# DM1098EMB_TopLevel.net
KiCad netlist of a schematic drawn in Altium Designer
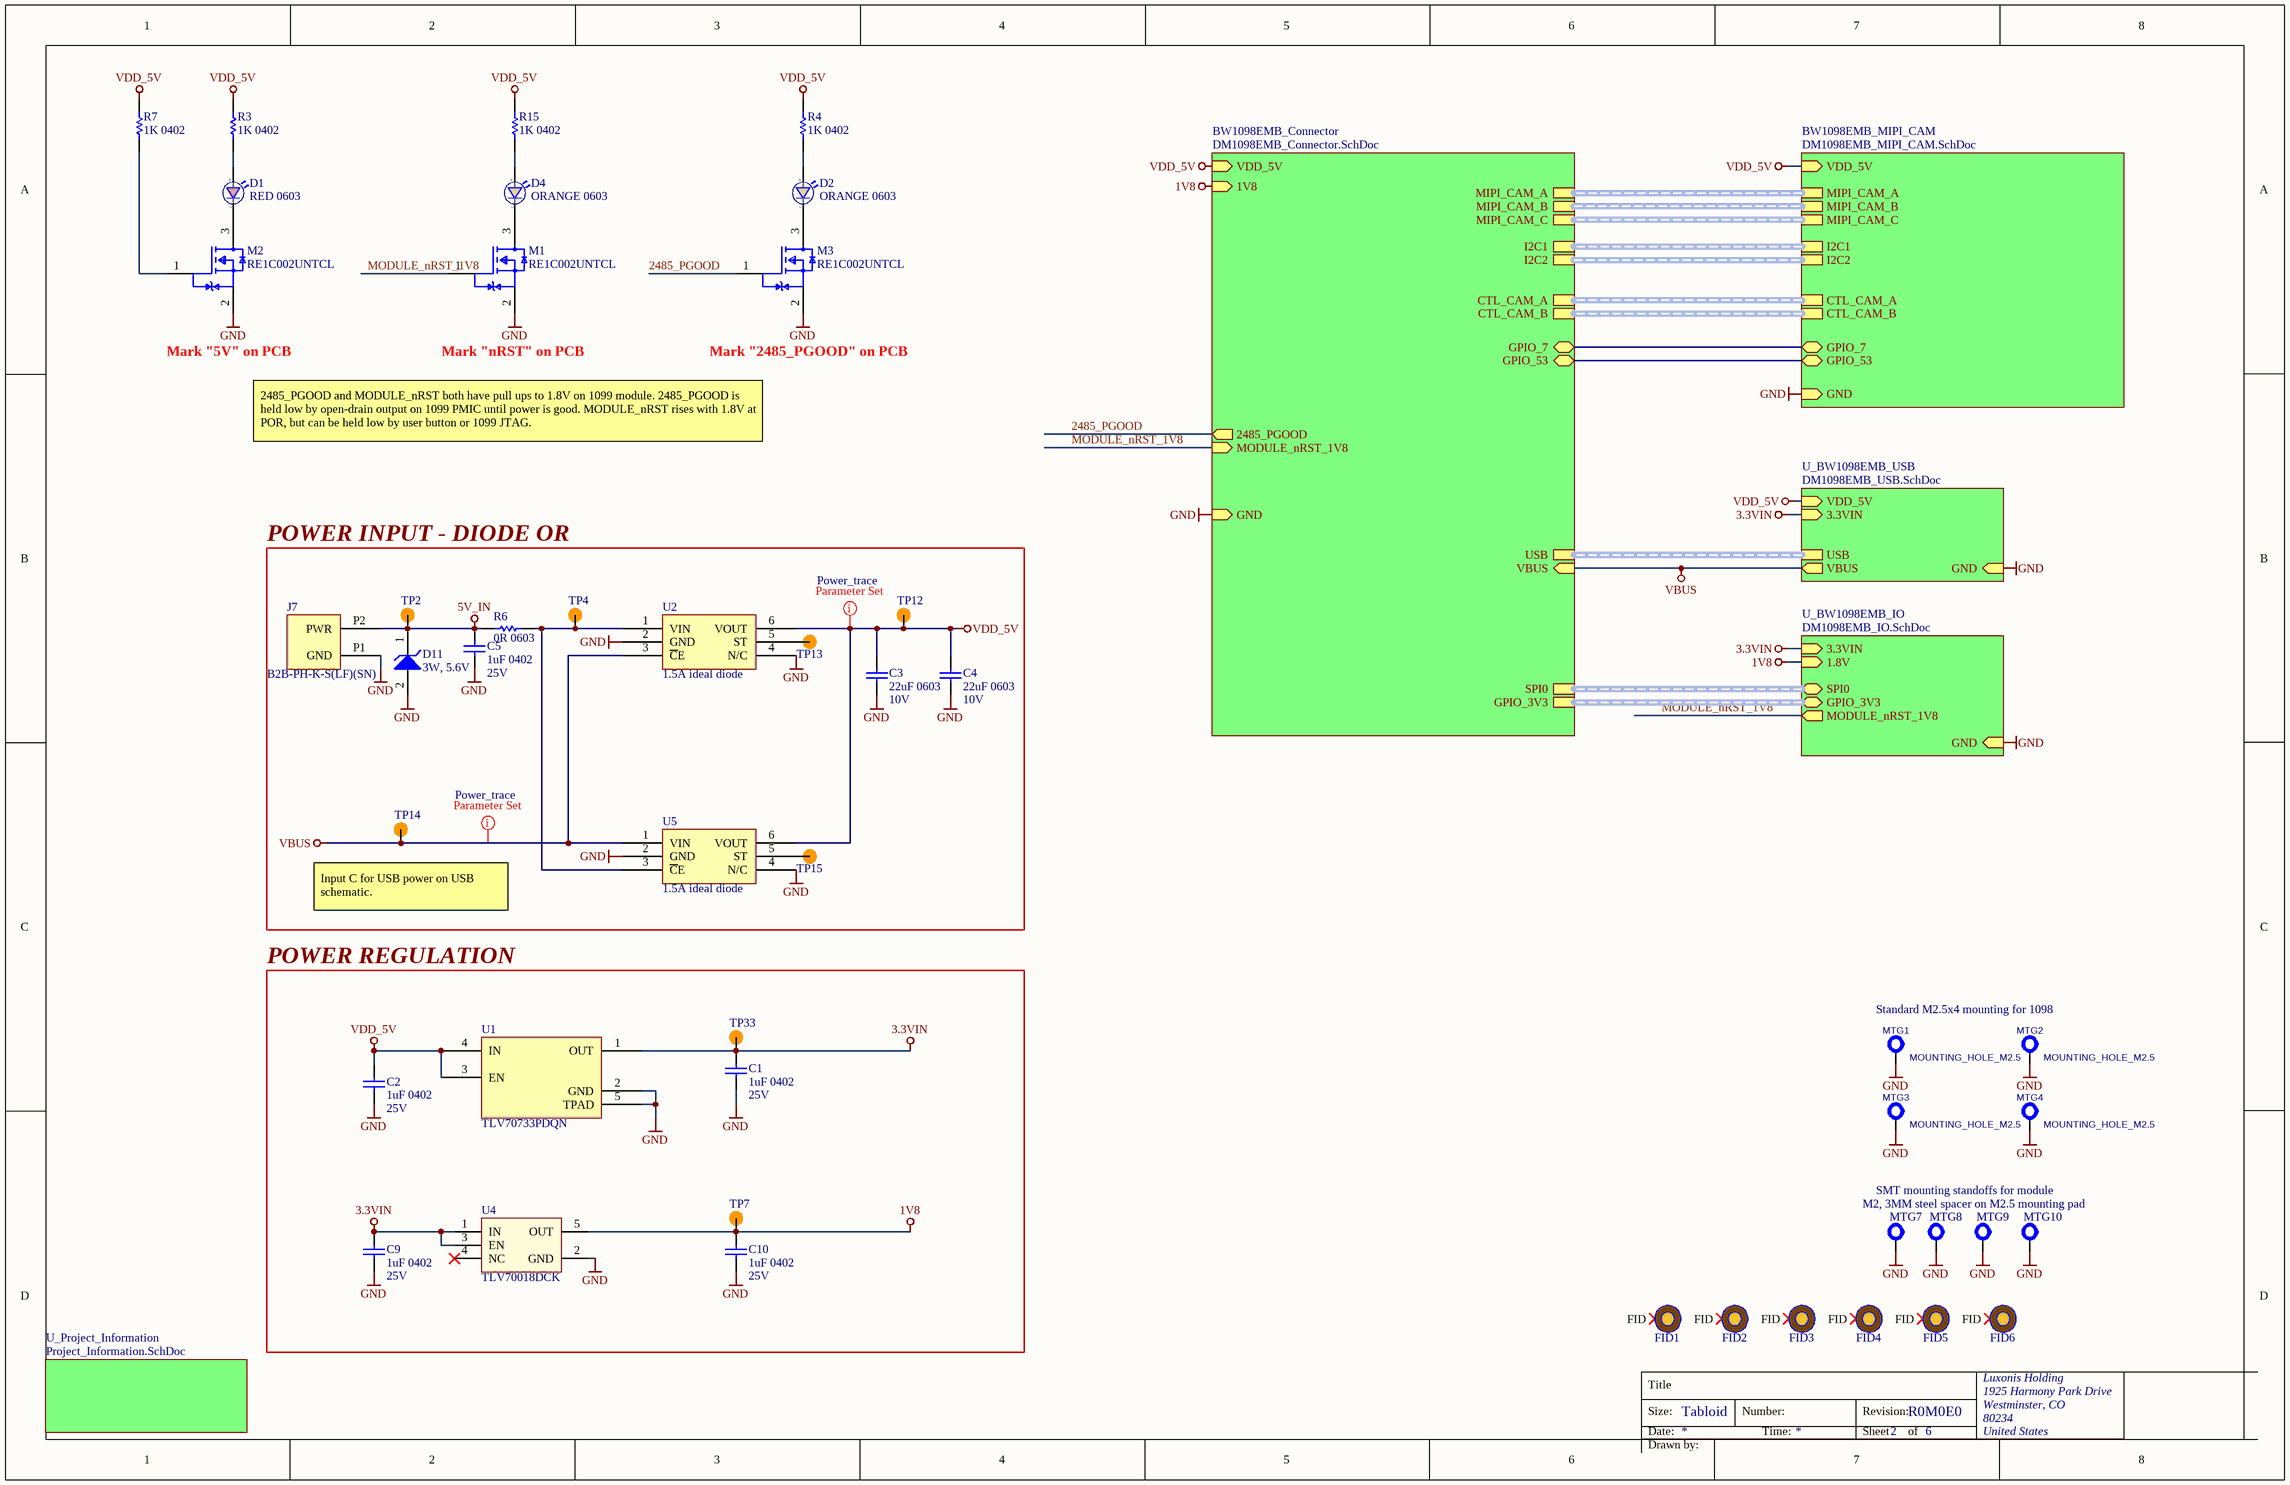
[diagram p0: DM1098EMB_TopLevel.SchDoc]

(export (version "E")
  (design (tool "Eeschema 10.0.6"))
  (components
    (comp (ref "C1")
      (value "1uF 0402")
      (footprint "CAP_Altium_Vault_Generic:CAPC0402(1005)70_N")
      (description "CAP CER 1UF 25V X5R 0402 10%")
      (fields
        (field (name "TOLERANCE") "10%")
        (field (name "VOLTAGE") "25V")
        (field (name "VOLTAGE RATING") "25V")
      )
      (libsource (lib "LuxonisMaster") (part "GRM155R61E105KA12D"))
    )
    (comp (ref "C2")
      (value "1uF 0402")
      (footprint "CAP_Altium_Vault_Generic:CAPC0402(1005)70_N")
      (description "CAP CER 1UF 25V X5R 0402 10%")
      (fields
        (field (name "TOLERANCE") "10%")
        (field (name "VOLTAGE") "25V")
        (field (name "VOLTAGE RATING") "25V")
      )
      (libsource (lib "LuxonisMaster") (part "GRM155R61E105KA12D"))
    )
    (comp (ref "C3")
      (value "22uF 0603")
      (footprint "CAP_Altium_Vault_Generic:CAPC0603(1608)100_N")
      (description "CAP CER 22UF 10V X5R 0603 20%")
      (fields (field (name "TOLERANCE") "20%") (field (name "VOLTAGE RATING") "10V"))
      (libsource (lib "LuxonisMaster") (part "GRM188R61A226ME15D"))
    )
    (comp (ref "C4")
      (value "22uF 0603")
      (footprint "CAP_Altium_Vault_Generic:CAPC0603(1608)100_N")
      (description "CAP CER 22UF 10V X5R 0603 20%")
      (fields (field (name "TOLERANCE") "20%") (field (name "VOLTAGE RATING") "10V"))
      (libsource (lib "LuxonisMaster") (part "GRM188R61A226ME15D"))
    )
    (comp (ref "C5")
      (value "1uF 0402")
      (footprint "CAP_Altium_Vault_Generic:CAPC0402(1005)70_N")
      (description "CAP CER 1UF 25V X5R 0402 10%")
      (fields
        (field (name "TOLERANCE") "10%")
        (field (name "VOLTAGE") "25V")
        (field (name "VOLTAGE RATING") "25V")
      )
      (libsource (lib "LuxonisMaster") (part "GRM155R61E105KA12D"))
    )
    (comp (ref "C9")
      (value "1uF 0402")
      (footprint "CAP_Altium_Vault_Generic:CAPC0402(1005)70_N")
      (description "CAP CER 1UF 25V X5R 0402 10%")
      (fields
        (field (name "TOLERANCE") "10%")
        (field (name "VOLTAGE") "25V")
        (field (name "VOLTAGE RATING") "25V")
      )
      (libsource (lib "LuxonisMaster") (part "GRM155R61E105KA12D"))
    )
    (comp (ref "C10")
      (value "1uF 0402")
      (footprint "CAP_Altium_Vault_Generic:CAPC0402(1005)70_N")
      (description "CAP CER 1UF 25V X5R 0402 10%")
      (fields
        (field (name "TOLERANCE") "10%")
        (field (name "VOLTAGE") "25V")
        (field (name "VOLTAGE RATING") "25V")
      )
      (libsource (lib "LuxonisMaster") (part "GRM155R61E105KA12D"))
    )
    (comp (ref "D1")
      (value "RED 0603")
      (footprint "LuxonisMaster:SML_D1xx8W")
      (description "LED RED DIFFUSED 0603 SMD Red 620nm LED Indication - Discrete 2.2V 0603 (1608 Metric)")
      (libsource (lib "LuxonisMaster") (part "SML-D12U8WT86"))
    )
    (comp (ref "D2")
      (value "ORANGE 0603")
      (footprint "LuxonisMaster:SML_D1xx8W")
      (description "LED ORANGE DIFFUSED 0603 SMD Orange 605nm LED Indication - Discrete 2.2V 0603 (1608 Metric)")
      (libsource (lib "LuxonisMaster") (part "SML-D12D8WT86"))
    )
    (comp (ref "D4")
      (value "ORANGE 0603")
      (footprint "LuxonisMaster:SML_D1xx8W")
      (description "LED ORANGE DIFFUSED 0603 SMD Orange 605nm LED Indication - Discrete 2.2V 0603 (1608 Metric)")
      (libsource (lib "LuxonisMaster") (part "SML-D12D8WT86"))
    )
    (comp (ref "D11")
      (value "3W, 5.6V")
      (footprint "DM1092_R0M0E0:1SMB5919BT3G")
      (description "DIODE ZENER 5.6V 3W SMB")
      (fields (field (name "TOLERANCE") "5%"))
      (libsource (lib "DM1092_R0M0E0") (part "1SMB5919BT3G"))
    )
    (comp (ref "FID1")
      (value "FIDUCIAL_ROUND_1MM")
      (footprint "LuxonisMaster:FIDUCIAL_ROUND_1MM")
      (description "Fiducial with various available footprints")
      (libsource (lib "LuxonisMaster") (part "FIDUCIAL"))
    )
    (comp (ref "FID2")
      (value "FIDUCIAL_ROUND_1MM")
      (footprint "LuxonisMaster:FIDUCIAL_ROUND_1MM")
      (description "Fiducial with various available footprints")
      (libsource (lib "LuxonisMaster") (part "FIDUCIAL"))
    )
    (comp (ref "FID3")
      (value "FIDUCIAL_ROUND_1MM")
      (footprint "LuxonisMaster:FIDUCIAL_ROUND_1MM")
      (description "Fiducial with various available footprints")
      (libsource (lib "LuxonisMaster") (part "FIDUCIAL"))
    )
    (comp (ref "FID4")
      (value "FIDUCIAL_ROUND_1MM")
      (footprint "LuxonisMaster:FIDUCIAL_ROUND_1MM")
      (description "Fiducial with various available footprints")
      (libsource (lib "LuxonisMaster") (part "FIDUCIAL"))
    )
    (comp (ref "FID5")
      (value "FIDUCIAL_ROUND_1MM")
      (footprint "LuxonisMaster:FIDUCIAL_ROUND_1MM")
      (description "Fiducial with various available footprints")
      (libsource (lib "LuxonisMaster") (part "FIDUCIAL"))
    )
    (comp (ref "FID6")
      (value "FIDUCIAL_ROUND_1MM")
      (footprint "LuxonisMaster:FIDUCIAL_ROUND_1MM")
      (description "Fiducial with various available footprints")
      (libsource (lib "LuxonisMaster") (part "FIDUCIAL"))
    )
    (comp (ref "J7")
      (value "B2B-PH-K-S(LF)(SN)")
      (footprint "LuxonisMaster:B2B-PH-K-S(LF)(SN)")
      (description "CONN HEADER VERT 2POS 2MM")
      (libsource (lib "LuxonisMaster") (part "B2B-PH-K-S(LF)(SN)"))
    )
    (comp (ref "M1")
      (value "RE1C002UNTCL")
      (footprint "LuxonisMaster:RE1C002UNTCL")
      (description "MOSFET N-CH 20V 0.2A EMT3")
      (libsource (lib "LuxonisMaster") (part "RE1C002UNTCL"))
    )
    (comp (ref "M2")
      (value "RE1C002UNTCL")
      (footprint "LuxonisMaster:RE1C002UNTCL")
      (description "MOSFET N-CH 20V 0.2A EMT3")
      (libsource (lib "LuxonisMaster") (part "RE1C002UNTCL"))
    )
    (comp (ref "M3")
      (value "RE1C002UNTCL")
      (footprint "LuxonisMaster:RE1C002UNTCL")
      (description "MOSFET N-CH 20V 0.2A EMT3")
      (libsource (lib "LuxonisMaster") (part "RE1C002UNTCL"))
    )
    (comp (ref "MTG1")
      (value "MOUNTING_HOLE_M2.5")
      (footprint "LuxonisMaster:MOUNTING_HOLE_M2.5")
      (description "=CurrentFootprint")
      (libsource (lib "LuxonisMaster") (part "MP_Mounting-Holes"))
    )
    (comp (ref "MTG2")
      (value "MOUNTING_HOLE_M2.5")
      (footprint "LuxonisMaster:MOUNTING_HOLE_M2.5")
      (description "=CurrentFootprint")
      (libsource (lib "LuxonisMaster") (part "MP_Mounting-Holes"))
    )
    (comp (ref "MTG3")
      (value "MOUNTING_HOLE_M2.5")
      (footprint "LuxonisMaster:MOUNTING_HOLE_M2.5")
      (description "=CurrentFootprint")
      (libsource (lib "LuxonisMaster") (part "MP_Mounting-Holes"))
    )
    (comp (ref "MTG4")
      (value "MOUNTING_HOLE_M2.5")
      (footprint "LuxonisMaster:MOUNTING_HOLE_M2.5")
      (description "=CurrentFootprint")
      (libsource (lib "LuxonisMaster") (part "MP_Mounting-Holes"))
    )
    (comp (ref "MTG7")
      (value "M2, 3MM steel spacer on M2.5 mounting pad")
      (footprint "LuxonisMaster:9774030243R")
      (description "MP ROUND STANDOFF M2X0.4 STEEL 3MM")
      (libsource (lib "LuxonisMaster") (part "9774030243R"))
    )
    (comp (ref "MTG8")
      (value "M2, 3MM steel spacer on M2.5 mounting pad")
      (footprint "LuxonisMaster:9774030243R")
      (description "MP ROUND STANDOFF M2X0.4 STEEL 3MM")
      (libsource (lib "LuxonisMaster") (part "9774030243R"))
    )
    (comp (ref "MTG9")
      (value "M2, 3MM steel spacer on M2.5 mounting pad")
      (footprint "LuxonisMaster:9774030243R")
      (description "MP ROUND STANDOFF M2X0.4 STEEL 3MM")
      (libsource (lib "LuxonisMaster") (part "9774030243R"))
    )
    (comp (ref "MTG10")
      (value "M2, 3MM steel spacer on M2.5 mounting pad")
      (footprint "LuxonisMaster:9774030243R")
      (description "MP ROUND STANDOFF M2X0.4 STEEL 3MM")
      (libsource (lib "LuxonisMaster") (part "9774030243R"))
    )
    (comp (ref "R3")
      (value "1K 0402")
      (footprint "RES_Altium_Vault_Generic:RESC0402(1005)_N")
      (fields (field (name "TOLERANCE") "1%"))
      (libsource (lib "LuxonisMaster") (part "RC0402FR-071KL"))
    )
    (comp (ref "R4")
      (value "1K 0402")
      (footprint "RES_Altium_Vault_Generic:RESC0402(1005)_N")
      (fields (field (name "TOLERANCE") "1%"))
      (libsource (lib "LuxonisMaster") (part "RC0402FR-071KL"))
    )
    (comp (ref "R6")
      (value "0R 0603")
      (footprint "RES_Altium_Vault_Generic:RESC0603(1608)_N")
      (fields (field (name "TOLERANCE") "5%"))
      (libsource (lib "LuxonisMaster") (part "CRCW06030000Z0EA"))
    )
    (comp (ref "R7")
      (value "1K 0402")
      (footprint "RES_Altium_Vault_Generic:RESC0402(1005)_N")
      (fields (field (name "TOLERANCE") "1%"))
      (libsource (lib "LuxonisMaster") (part "RC0402FR-071KL"))
    )
    (comp (ref "R15")
      (value "1K 0402")
      (footprint "RES_Altium_Vault_Generic:RESC0402(1005)_N")
      (fields (field (name "TOLERANCE") "1%"))
      (libsource (lib "LuxonisMaster") (part "RC0402FR-071KL"))
    )
    (comp (ref "TP2")
      (value "TP100_200_NS")
      (footprint "LuxonisMaster:TP100_200_NS")
      (libsource (lib "LuxonisMaster") (part "TEST_POINT"))
    )
    (comp (ref "TP4")
      (value "TP100_200_NS")
      (footprint "LuxonisMaster:TP100_200_NS")
      (libsource (lib "LuxonisMaster") (part "TEST_POINT"))
    )
    (comp (ref "TP7")
      (value "TP100_200_NS")
      (footprint "LuxonisMaster:TP100_200_NS")
      (libsource (lib "LuxonisMaster") (part "TEST_POINT"))
    )
    (comp (ref "TP12")
      (value "TP100_200_NS")
      (footprint "LuxonisMaster:TP100_200_NS")
      (libsource (lib "LuxonisMaster") (part "TEST_POINT"))
    )
    (comp (ref "TP13")
      (value "TP100_200_NS")
      (footprint "LuxonisMaster:TP100_200_NS")
      (libsource (lib "LuxonisMaster") (part "TEST_POINT"))
    )
    (comp (ref "TP14")
      (value "TP100_200_NS")
      (footprint "LuxonisMaster:TP100_200_NS")
      (libsource (lib "LuxonisMaster") (part "TEST_POINT"))
    )
    (comp (ref "TP15")
      (value "TP100_200_NS")
      (footprint "LuxonisMaster:TP100_200_NS")
      (libsource (lib "LuxonisMaster") (part "TEST_POINT"))
    )
    (comp (ref "TP33")
      (value "TP100_200_NS")
      (footprint "LuxonisMaster:TP100_200_NS")
      (libsource (lib "LuxonisMaster") (part "TEST_POINT"))
    )
    (comp (ref "U1")
      (value "TLV70733PDQN")
      (footprint "LuxonisMaster:TLV70733PDQN")
      (description "IC REG LINEAR 3.3V 200MA 4X2SON Linear Voltage Regulator IC  1 Output  200mA 4-X2SON (1x1)")
      (libsource (lib "LuxonisMaster") (part "TLV70733PDQN"))
    )
    (comp (ref "U2")
      (value "1.5A ideal diode")
      (footprint "LuxonisMaster:LM66100DCKR")
      (description "IC OR CTRLR IDEAL DIODE SC70-6")
      (libsource (lib "LuxonisMaster") (part "LM66100DCKR"))
    )
    (comp (ref "U4")
      (value "TLV70018DCK")
      (footprint "LuxonisMaster:TLV70018DCK")
      (description "IC REG LINEAR 1.8V 200MA SC70-5 Linear Voltage Regulator IC  1 Output  200mA SC-70-5")
      (libsource (lib "LuxonisMaster") (part "TLV70018DCK"))
    )
    (comp (ref "U5")
      (value "1.5A ideal diode")
      (footprint "LuxonisMaster:LM66100DCKR")
      (description "IC OR CTRLR IDEAL DIODE SC70-6")
      (libsource (lib "LuxonisMaster") (part "LM66100DCKR"))
    )
  )
  (nets
    (net (code "1") (name "/2485_PGOOD") (class "Default")
      (node (ref "M3") (pin "1") (pinfunction "Gate_1") (pintype "passive"))
    )
    (net (code "12") (name "/MODULE_nRST_1V8") (class "Default")
      (node (ref "M1") (pin "1") (pinfunction "Gate_1") (pintype "passive"))
    )
    (net (code "15") (name "1V8") (class "Default")
      (node (ref "C10") (pin "2") (pinfunction "2_2") (pintype "passive"))
      (node (ref "TP7") (pin "1") (pintype "passive"))
      (node (ref "U4") (pin "5") (pinfunction "OUT_5") (pintype "passive"))
    )
    (net (code "16") (name "3.3VIN") (class "Default")
      (node (ref "C1") (pin "2") (pinfunction "2_2") (pintype "passive"))
      (node (ref "C9") (pin "2") (pinfunction "2_2") (pintype "passive"))
      (node (ref "TP33") (pin "1") (pintype "passive"))
      (node (ref "U1") (pin "1") (pinfunction "OUT_1") (pintype "power_in"))
      (node (ref "U4") (pin "1") (pinfunction "IN_1") (pintype "passive"))
      (node (ref "U4") (pin "3") (pinfunction "EN_3") (pintype "passive"))
    )
    (net (code "17") (name "5V_IN") (class "Default")
      (node (ref "C5") (pin "2") (pinfunction "2_2") (pintype "passive"))
      (node (ref "D11") (pin "1") (pinfunction "K_1") (pintype "passive"))
      (node (ref "J7") (pin "P2") (pinfunction "PWR_P2") (pintype "passive"))
      (node (ref "R6") (pin "1") (pinfunction "1_1") (pintype "passive"))
      (node (ref "TP2") (pin "1") (pintype "passive"))
    )
    (net (code "18") (name "GND") (class "Default")
      (node (ref "C1") (pin "1") (pinfunction "1_1") (pintype "passive"))
      (node (ref "C10") (pin "1") (pinfunction "1_1") (pintype "passive"))
      (node (ref "C2") (pin "1") (pinfunction "1_1") (pintype "passive"))
      (node (ref "C3") (pin "1") (pinfunction "1_1") (pintype "passive"))
      (node (ref "C4") (pin "1") (pinfunction "1_1") (pintype "passive"))
      (node (ref "C5") (pin "1") (pinfunction "1_1") (pintype "passive"))
      (node (ref "C9") (pin "1") (pinfunction "1_1") (pintype "passive"))
      (node (ref "D11") (pin "2") (pinfunction "A_2") (pintype "passive"))
      (node (ref "J7") (pin "P1") (pinfunction "GND_P1") (pintype "passive"))
      (node (ref "M1") (pin "2") (pinfunction "Source_2") (pintype "passive"))
      (node (ref "M2") (pin "2") (pinfunction "Source_2") (pintype "passive"))
      (node (ref "M3") (pin "2") (pinfunction "Source_2") (pintype "passive"))
      (node (ref "MTG1") (pin "1") (pintype "passive"))
      (node (ref "MTG10") (pin "1") (pintype "passive"))
      (node (ref "MTG2") (pin "1") (pintype "passive"))
      (node (ref "MTG3") (pin "1") (pintype "passive"))
      (node (ref "MTG4") (pin "1") (pintype "passive"))
      (node (ref "MTG7") (pin "1") (pintype "passive"))
      (node (ref "MTG8") (pin "1") (pintype "passive"))
      (node (ref "MTG9") (pin "1") (pintype "passive"))
      (node (ref "U1") (pin "2") (pinfunction "GND_2") (pintype "power_in"))
      (node (ref "U1") (pin "5") (pinfunction "TPAD_5") (pintype "passive"))
      (node (ref "U2") (pin "2") (pinfunction "GND_2") (pintype "passive"))
      (node (ref "U2") (pin "4") (pinfunction "N/C_4") (pintype "passive"))
      (node (ref "U4") (pin "2") (pinfunction "GND_2") (pintype "passive"))
      (node (ref "U5") (pin "2") (pinfunction "GND_2") (pintype "passive"))
      (node (ref "U5") (pin "4") (pinfunction "N/C_4") (pintype "passive"))
    )
    (net (code "19") (name "Net-(D1-A)") (class "Default")
      (node (ref "D1") (pin "2") (pinfunction "A_2") (pintype "passive"))
      (node (ref "R3") (pin "1") (pinfunction "1_1") (pintype "passive"))
    )
    (net (code "20") (name "Net-(D1-C)") (class "Default")
      (node (ref "D1") (pin "1") (pinfunction "C_1") (pintype "passive"))
      (node (ref "M2") (pin "3") (pinfunction "Drain_3") (pintype "passive"))
    )
    (net (code "21") (name "Net-(D2-A)") (class "Default")
      (node (ref "D2") (pin "2") (pinfunction "A_2") (pintype "passive"))
      (node (ref "R4") (pin "1") (pinfunction "1_1") (pintype "passive"))
    )
    (net (code "22") (name "Net-(D2-C)") (class "Default")
      (node (ref "D2") (pin "1") (pinfunction "C_1") (pintype "passive"))
      (node (ref "M3") (pin "3") (pinfunction "Drain_3") (pintype "passive"))
    )
    (net (code "23") (name "Net-(D4-A)") (class "Default")
      (node (ref "D4") (pin "2") (pinfunction "A_2") (pintype "passive"))
      (node (ref "R15") (pin "1") (pinfunction "1_1") (pintype "passive"))
    )
    (net (code "24") (name "Net-(D4-C)") (class "Default")
      (node (ref "D4") (pin "1") (pinfunction "C_1") (pintype "passive"))
      (node (ref "M1") (pin "3") (pinfunction "Drain_3") (pintype "passive"))
    )
    (net (code "25") (name "Net-(M2-Gate)") (class "Default")
      (node (ref "M2") (pin "1") (pinfunction "Gate_1") (pintype "passive"))
      (node (ref "R7") (pin "1") (pinfunction "1_1") (pintype "passive"))
    )
    (net (code "26") (name "Net-(U2-ST)") (class "Default")
      (node (ref "TP13") (pin "1") (pintype "passive"))
      (node (ref "U2") (pin "5") (pinfunction "ST_5") (pintype "passive"))
    )
    (net (code "27") (name "Net-(U2-VIN)") (class "Default")
      (node (ref "R6") (pin "2") (pinfunction "2_2") (pintype "passive"))
      (node (ref "TP4") (pin "1") (pintype "passive"))
      (node (ref "U2") (pin "1") (pinfunction "VIN_1") (pintype "passive"))
      (node (ref "U5") (pin "3") (pinfunction "~{C}E_3") (pintype "passive"))
    )
    (net (code "28") (name "Net-(U5-ST)") (class "Default")
      (node (ref "TP15") (pin "1") (pintype "passive"))
      (node (ref "U5") (pin "5") (pinfunction "ST_5") (pintype "passive"))
    )
    (net (code "29") (name "VBUS") (class "Default")
      (node (ref "TP14") (pin "1") (pintype "passive"))
      (node (ref "U2") (pin "3") (pinfunction "~{C}E_3") (pintype "passive"))
      (node (ref "U5") (pin "1") (pinfunction "VIN_1") (pintype "passive"))
    )
    (net (code "30") (name "VDD_5V") (class "Default")
      (node (ref "C2") (pin "2") (pinfunction "2_2") (pintype "passive"))
      (node (ref "C3") (pin "2") (pinfunction "2_2") (pintype "passive"))
      (node (ref "C4") (pin "2") (pinfunction "2_2") (pintype "passive"))
      (node (ref "R15") (pin "2") (pinfunction "2_2") (pintype "passive"))
      (node (ref "R3") (pin "2") (pinfunction "2_2") (pintype "passive"))
      (node (ref "R4") (pin "2") (pinfunction "2_2") (pintype "passive"))
      (node (ref "R7") (pin "2") (pinfunction "2_2") (pintype "passive"))
      (node (ref "TP12") (pin "1") (pintype "passive"))
      (node (ref "U1") (pin "3") (pinfunction "EN_3") (pintype "power_in"))
      (node (ref "U1") (pin "4") (pinfunction "IN_4") (pintype "power_in"))
      (node (ref "U2") (pin "6") (pinfunction "VOUT_6") (pintype "passive"))
      (node (ref "U5") (pin "6") (pinfunction "VOUT_6") (pintype "passive"))
    )
    (net (code "31") (name "unconnected-(FID1-PadFID)") (class "Default")
      (node (ref "FID1") (pin "FID") (pinfunction "FID_FID") (pintype "input+no_connect"))
    )
    (net (code "32") (name "unconnected-(FID2-PadFID)") (class "Default")
      (node (ref "FID2") (pin "FID") (pinfunction "FID_FID") (pintype "input+no_connect"))
    )
    (net (code "33") (name "unconnected-(FID3-PadFID)") (class "Default")
      (node (ref "FID3") (pin "FID") (pinfunction "FID_FID") (pintype "input+no_connect"))
    )
    (net (code "34") (name "unconnected-(FID4-PadFID)") (class "Default")
      (node (ref "FID4") (pin "FID") (pinfunction "FID_FID") (pintype "input+no_connect"))
    )
    (net (code "35") (name "unconnected-(FID5-PadFID)") (class "Default")
      (node (ref "FID5") (pin "FID") (pinfunction "FID_FID") (pintype "input+no_connect"))
    )
    (net (code "36") (name "unconnected-(FID6-PadFID)") (class "Default")
      (node (ref "FID6") (pin "FID") (pinfunction "FID_FID") (pintype "input+no_connect"))
    )
    (net (code "37") (name "unconnected-(U4-NC-Pad4)") (class "Default")
      (node (ref "U4") (pin "4") (pinfunction "NC_4") (pintype "passive+no_connect"))
    )
  )
)
